# Touch_pad.net
KiCad netlist of a schematic drawn in Altium Designer
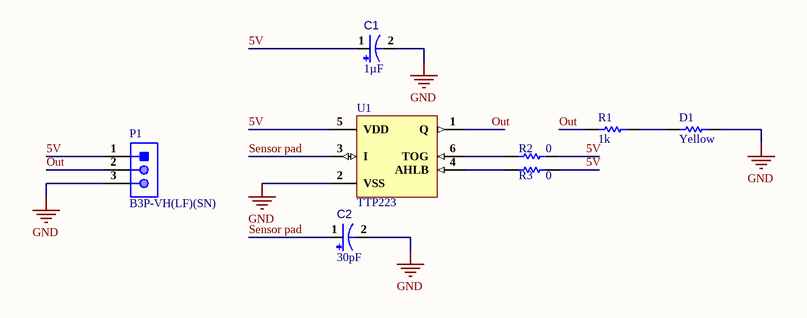
[diagram p0:  Touch_pad.SchDoc]

(export (version "E")
  (design (tool "Eeschema 10.0.6"))
  (components
    (comp (ref "C1")
      (value "1µF")
      (footprint "CAPC0805(2012)145_L")
      (description "Chip Capacitor, 1 uF, +/-10%, 25 V, 0805 (2012 Metric)")
      (fields (field (name "TOLERANCE") "10%") (field (name "Comment") "Capacitor 1 uF +/- 10% 25 V 0805"))
      (libsource (lib "University of Technology") (part "CAP-P-2"))
    )
    (comp (ref "C2")
      (value "30pF")
      (footprint "CAPC0805(2012)145_L")
      (description "Chip Capacitor, 1 uF, +/-10%, 25 V, 0805 (2012 Metric)")
      (fields (field (name "TOLERANCE") "10%") (field (name "Comment") "Capacitor 1 uF +/- 10% 25 V 0805"))
      (libsource (lib "University of Technology") (part "CAP-P-2"))
    )
    (comp (ref "D1")
      (value "Yellow")
      (footprint "RESC0805(2012)_L")
      (description "Chip Resistor, 1 KOhm, +/- 1%, 0.125 W, -55 to 155 degC, 0805 (2013 Metric)")
      (fields (field (name "POWER") "125mW") (field (name "TOLERANCE") "1%"))
      (libsource (lib "University of Technology") (part "RES-2"))
    )
    (comp (ref "P1")
      (value "B3P-VH(LF)(SN)")
      (footprint "JST-B3P-VH(LF)(SN)-3_V")
      (fields (field (name "MANUFACTURER") "JST"))
      (libsource (lib "University of Technology") (part "CN-1P-M-R3"))
    )
    (comp (ref "R1")
      (value "1k")
      (footprint "RESC0805(2012)_L")
      (description "Chip Resistor, 1 KOhm, +/- 1%, 0.125 W, -55 to 155 degC, 0805 (2013 Metric)")
      (fields (field (name "POWER") "125mW") (field (name "TOLERANCE") "1%"))
      (libsource (lib "University of Technology") (part "RES-2"))
    )
    (comp (ref "R2")
      (value "0")
      (footprint "RESC0805(2012)_L")
      (description "Chip Resistor, 0 Ohm, +/- 1%, 125 mW, -55 to 155 degC, 0805 (2012 Metric)")
      (fields (field (name "POWER") "125mW") (field (name "TOLERANCE") "1%"))
      (libsource (lib "University of Technology") (part "RES-2"))
    )
    (comp (ref "R3")
      (value "0")
      (footprint "RESC0805(2012)_L")
      (description "Chip Resistor, 0 Ohm, +/- 1%, 125 mW, -55 to 155 degC, 0805 (2012 Metric)")
      (fields (field (name "POWER") "125mW") (field (name "TOLERANCE") "1%"))
      (libsource (lib "University of Technology") (part "RES-2"))
    )
    (comp (ref "U1")
      (value "TTP223")
      (footprint "TTP223-SOT-23-6L")
      (description "The TTP223-BA6/TTP223N-BA6 TonTouchTM is a touch pad detector IC")
      (libsource (lib "University of Technology") (part "TTP223"))
    )
  )
  (nets
    (net (code "1") (name "/5V") (class "Default")
      (node (ref "C1") (pin "1") (pinfunction "1_1") (pintype "passive"))
      (node (ref "P1") (pin "1") (pinfunction "1_1") (pintype "passive"))
      (node (ref "R2") (pin "2") (pinfunction "2_2") (pintype "passive"))
      (node (ref "R3") (pin "2") (pinfunction "2_2") (pintype "passive"))
      (node (ref "U1") (pin "5") (pinfunction "VDD_5") (pintype "power_in"))
    )
    (net (code "2") (name "/Out") (class "Default")
      (node (ref "P1") (pin "2") (pinfunction "2_2") (pintype "passive"))
      (node (ref "R1") (pin "1") (pinfunction "1_1") (pintype "passive"))
      (node (ref "U1") (pin "1") (pinfunction "Q_1") (pintype "output"))
    )
    (net (code "3") (name "/Sensor pad") (class "Default")
      (node (ref "C2") (pin "1") (pinfunction "1_1") (pintype "passive"))
      (node (ref "U1") (pin "3") (pinfunction "I_3") (pintype "bidirectional"))
    )
    (net (code "4") (name "GND") (class "Default")
      (node (ref "C1") (pin "2") (pinfunction "2_2") (pintype "passive"))
      (node (ref "C2") (pin "2") (pinfunction "2_2") (pintype "passive"))
      (node (ref "D1") (pin "2") (pinfunction "2_2") (pintype "passive"))
      (node (ref "P1") (pin "3") (pinfunction "3_3") (pintype "passive"))
      (node (ref "U1") (pin "2") (pinfunction "VSS_2") (pintype "power_in"))
    )
    (net (code "5") (name "Net-(D1-Pad1)") (class "Default")
      (node (ref "D1") (pin "1") (pinfunction "1_1") (pintype "passive"))
      (node (ref "R1") (pin "2") (pinfunction "2_2") (pintype "passive"))
    )
    (net (code "6") (name "Net-(U1-AHLB)") (class "Default")
      (node (ref "R3") (pin "1") (pinfunction "1_1") (pintype "passive"))
      (node (ref "U1") (pin "4") (pinfunction "AHLB_4") (pintype "input"))
    )
    (net (code "7") (name "Net-(U1-TOG)") (class "Default")
      (node (ref "R2") (pin "1") (pinfunction "1_1") (pintype "passive"))
      (node (ref "U1") (pin "6") (pinfunction "TOG_6") (pintype "input"))
    )
  )
)
